# future_connector.net
KiCad netlist of a schematic drawn in Altium Designer
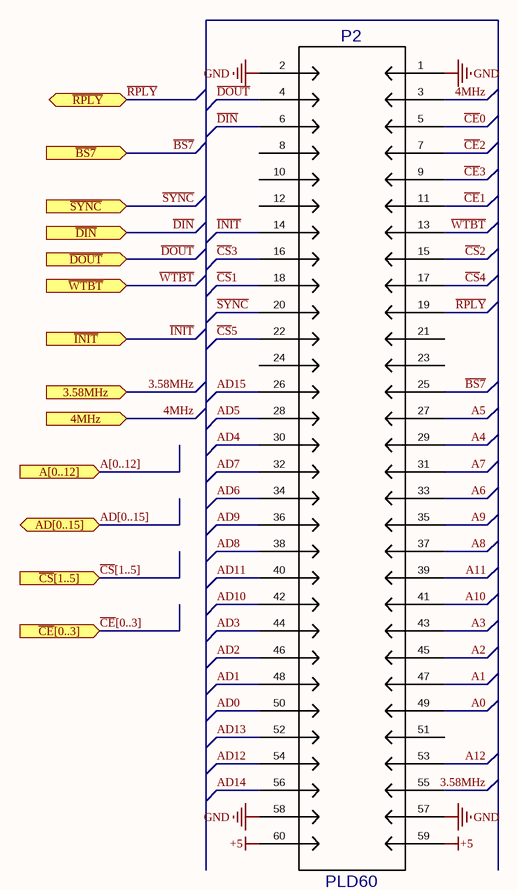
[diagram p0: future_connector.SchDoc]

(export (version "E")
  (design (tool "Eeschema 10.0.6"))
  (components
    (comp (ref "P2") (value "PLD60") (footprint "PLD60") (libsource (lib "my_components") (part "PLD60")))
  )
  (nets
    (net (code "1") (name "+5") (class "Default")
      (node (ref "P2") (pin "59") (pintype "passive"))
      (node (ref "P2") (pin "60") (pintype "passive"))
    )
    (net (code "2") (name "/3.58MHz") (class "Default") (node (ref "P2") (pin "55") (pintype "passive")))
    (net (code "3") (name "/4MHz") (class "Default") (node (ref "P2") (pin "3") (pintype "passive")))
    (net (code "4") (name "/A0") (class "Default") (node (ref "P2") (pin "49") (pintype "passive")))
    (net (code "5") (name "/A1") (class "Default") (node (ref "P2") (pin "47") (pintype "passive")))
    (net (code "6") (name "/A2") (class "Default") (node (ref "P2") (pin "45") (pintype "passive")))
    (net (code "7") (name "/A3") (class "Default") (node (ref "P2") (pin "43") (pintype "passive")))
    (net (code "8") (name "/A4") (class "Default") (node (ref "P2") (pin "29") (pintype "passive")))
    (net (code "9") (name "/A5") (class "Default") (node (ref "P2") (pin "27") (pintype "passive")))
    (net (code "10") (name "/A6") (class "Default") (node (ref "P2") (pin "33") (pintype "passive")))
    (net (code "11") (name "/A7") (class "Default") (node (ref "P2") (pin "31") (pintype "passive")))
    (net (code "12") (name "/A8") (class "Default") (node (ref "P2") (pin "37") (pintype "passive")))
    (net (code "13") (name "/A9") (class "Default") (node (ref "P2") (pin "35") (pintype "passive")))
    (net (code "14") (name "/A10") (class "Default") (node (ref "P2") (pin "41") (pintype "passive")))
    (net (code "15") (name "/A11") (class "Default") (node (ref "P2") (pin "39") (pintype "passive")))
    (net (code "16") (name "/A12") (class "Default") (node (ref "P2") (pin "53") (pintype "passive")))
    (net (code "17") (name "/AD0") (class "Default") (node (ref "P2") (pin "50") (pintype "passive")))
    (net (code "18") (name "/AD1") (class "Default") (node (ref "P2") (pin "48") (pintype "passive")))
    (net (code "19") (name "/AD2") (class "Default") (node (ref "P2") (pin "46") (pintype "passive")))
    (net (code "20") (name "/AD3") (class "Default") (node (ref "P2") (pin "44") (pintype "passive")))
    (net (code "21") (name "/AD4") (class "Default") (node (ref "P2") (pin "30") (pintype "passive")))
    (net (code "22") (name "/AD5") (class "Default") (node (ref "P2") (pin "28") (pintype "passive")))
    (net (code "23") (name "/AD6") (class "Default") (node (ref "P2") (pin "34") (pintype "passive")))
    (net (code "24") (name "/AD7") (class "Default") (node (ref "P2") (pin "32") (pintype "passive")))
    (net (code "25") (name "/AD8") (class "Default") (node (ref "P2") (pin "38") (pintype "passive")))
    (net (code "26") (name "/AD9") (class "Default") (node (ref "P2") (pin "36") (pintype "passive")))
    (net (code "27") (name "/AD10") (class "Default") (node (ref "P2") (pin "42") (pintype "passive")))
    (net (code "28") (name "/AD11") (class "Default") (node (ref "P2") (pin "40") (pintype "passive")))
    (net (code "29") (name "/AD12") (class "Default") (node (ref "P2") (pin "54") (pintype "passive")))
    (net (code "30") (name "/AD13") (class "Default") (node (ref "P2") (pin "52") (pintype "passive")))
    (net (code "31") (name "/AD14") (class "Default") (node (ref "P2") (pin "56") (pintype "passive")))
    (net (code "32") (name "/AD15") (class "Default") (node (ref "P2") (pin "26") (pintype "passive")))
    (net (code "35") (name "/~{BS7}") (class "Default") (node (ref "P2") (pin "25") (pintype "passive")))
    (net (code "36") (name "/~{CE}0") (class "Default") (node (ref "P2") (pin "5") (pintype "passive")))
    (net (code "37") (name "/~{CE}1") (class "Default") (node (ref "P2") (pin "11") (pintype "passive")))
    (net (code "38") (name "/~{CE}2") (class "Default") (node (ref "P2") (pin "7") (pintype "passive")))
    (net (code "39") (name "/~{CE}3") (class "Default") (node (ref "P2") (pin "9") (pintype "passive")))
    (net (code "41") (name "/~{CS}1") (class "Default") (node (ref "P2") (pin "18") (pintype "passive")))
    (net (code "42") (name "/~{CS}2") (class "Default") (node (ref "P2") (pin "15") (pintype "passive")))
    (net (code "43") (name "/~{CS}3") (class "Default") (node (ref "P2") (pin "16") (pintype "passive")))
    (net (code "44") (name "/~{CS}4") (class "Default") (node (ref "P2") (pin "17") (pintype "passive")))
    (net (code "45") (name "/~{CS}5") (class "Default") (node (ref "P2") (pin "22") (pintype "passive")))
    (net (code "47") (name "/~{DIN}") (class "Default") (node (ref "P2") (pin "6") (pintype "passive")))
    (net (code "48") (name "/~{DOUT}") (class "Default") (node (ref "P2") (pin "4") (pintype "passive")))
    (net (code "49") (name "/~{INIT}") (class "Default") (node (ref "P2") (pin "14") (pintype "passive")))
    (net (code "50") (name "/~{RPLY}") (class "Default") (node (ref "P2") (pin "19") (pintype "passive")))
    (net (code "51") (name "/~{SYNC}") (class "Default") (node (ref "P2") (pin "20") (pintype "passive")))
    (net (code "52") (name "/~{WTBT}") (class "Default") (node (ref "P2") (pin "13") (pintype "passive")))
    (net (code "53") (name "GND") (class "Default")
      (node (ref "P2") (pin "1") (pintype "passive"))
      (node (ref "P2") (pin "2") (pintype "passive"))
      (node (ref "P2") (pin "57") (pintype "passive"))
      (node (ref "P2") (pin "58") (pintype "passive"))
    )
    (net (code "54") (name "unconnected-(P2-Pad8)") (class "Default")
      (node (ref "P2") (pin "8") (pintype "passive"))
    )
    (net (code "55") (name "unconnected-(P2-Pad10)") (class "Default")
      (node (ref "P2") (pin "10") (pintype "passive"))
    )
    (net (code "56") (name "unconnected-(P2-Pad12)") (class "Default")
      (node (ref "P2") (pin "12") (pintype "passive"))
    )
    (net (code "57") (name "unconnected-(P2-Pad21)") (class "Default")
      (node (ref "P2") (pin "21") (pintype "passive"))
    )
    (net (code "58") (name "unconnected-(P2-Pad23)") (class "Default")
      (node (ref "P2") (pin "23") (pintype "passive"))
    )
    (net (code "59") (name "unconnected-(P2-Pad24)") (class "Default")
      (node (ref "P2") (pin "24") (pintype "passive"))
    )
    (net (code "60") (name "unconnected-(P2-Pad51)") (class "Default")
      (node (ref "P2") (pin "51") (pintype "passive"))
    )
  )
)
